# CadSoftElectronic.net
KiCad netlist of a schematic drawn in EAGLE
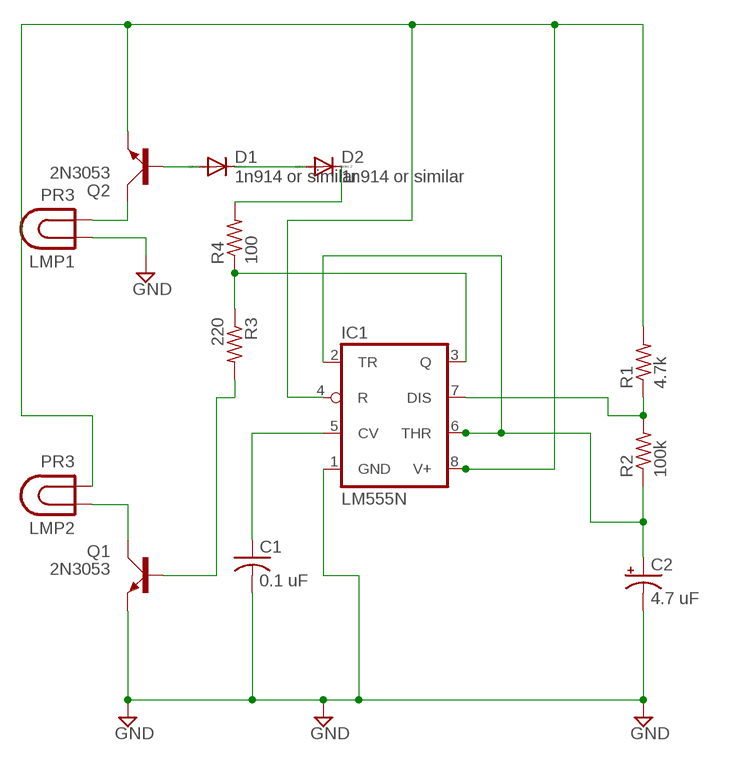
[diagram p0: schematic, sheet 1]

(export (version "E")
  (design (tool "Eeschema 10.0.6"))
  (components
    (comp (ref "C1")
      (value "0.1 uF")
      (footprint "eagle-import:C050-025X075")
      (libsource (lib "eagle-import") (part "C-US050-025X075"))
    )
    (comp (ref "C2")
      (value "4.7 uF")
      (footprint "eagle-import:E5-5")
      (libsource (lib "eagle-import") (part "CPOL-USE5-5"))
    )
    (comp (ref "D1")
      (value "1n914 or similar")
      (footprint "eagle-import:D-2.5")
      (libsource (lib "eagle-import") (part "DIODE-D-2.5"))
    )
    (comp (ref "D2")
      (value "1n914 or similar")
      (footprint "eagle-import:D-2.5")
      (libsource (lib "eagle-import") (part "DIODE-D-2.5"))
    )
    (comp (ref "IC1")
      (value "LM555N")
      (footprint "eagle-import:DIL08")
      (libsource (lib "eagle-import") (part "555NLM"))
    )
    (comp (ref "LMP1")
      (value "PR3")
      (footprint "eagle-import:LDH-5R")
      (libsource (lib "eagle-import") (part "LAMP"))
    )
    (comp (ref "LMP2")
      (value "PR3")
      (footprint "eagle-import:LDH-5R")
      (libsource (lib "eagle-import") (part "LAMP"))
    )
    (comp (ref "Q1")
      (value "2N3053")
      (footprint "eagle-import:TO39")
      (libsource (lib "eagle-import") (part "2N3053"))
    )
    (comp (ref "Q2")
      (value "2N3053")
      (footprint "eagle-import:TO39")
      (libsource (lib "eagle-import") (part "2N3053"))
    )
    (comp (ref "R1")
      (value "4.7k")
      (footprint "eagle-import:0207_2V")
      (libsource (lib "eagle-import") (part "R-US_0207/2V"))
    )
    (comp (ref "R2")
      (value "100k")
      (footprint "eagle-import:0207_2V")
      (libsource (lib "eagle-import") (part "R-US_0207/2V"))
    )
    (comp (ref "R3")
      (value "220")
      (footprint "eagle-import:0207_2V")
      (libsource (lib "eagle-import") (part "R-US_0207/2V"))
    )
    (comp (ref "R4")
      (value "100")
      (footprint "eagle-import:0207_2V")
      (libsource (lib "eagle-import") (part "R-US_0207/2V"))
    )
  )
  (nets
    (net (code "1") (name "GND") (class "Default")
      (node (ref "C1") (pin "2") (pinfunction "2_2") (pintype "passive"))
      (node (ref "C2") (pin "-") (pinfunction "-_-") (pintype "passive"))
      (node (ref "IC1") (pin "1") (pinfunction "GND_1") (pintype "power_in"))
      (node (ref "LMP1") (pin "1") (pinfunction "1_1") (pintype "passive"))
      (node (ref "Q1") (pin "1") (pinfunction "E_1") (pintype "passive"))
    )
    (net (code "2") (name "Net-(D1-PadC)") (class "Default")
      (node (ref "D1") (pin "C") (pinfunction "C_C") (pintype "passive"))
      (node (ref "D2") (pin "A") (pinfunction "A_A") (pintype "passive"))
    )
    (net (code "3") (name "Net-(D2-PadC)") (class "Default")
      (node (ref "D2") (pin "C") (pinfunction "C_C") (pintype "passive"))
      (node (ref "R4") (pin "2") (pinfunction "2_2") (pintype "passive"))
    )
    (net (code "4") (name "Net-(IC1-CV)") (class "Default")
      (node (ref "C1") (pin "1") (pinfunction "1_1") (pintype "passive"))
      (node (ref "IC1") (pin "5") (pinfunction "CV_5") (pintype "input"))
    )
    (net (code "5") (name "Net-(IC1-DIS)") (class "Default")
      (node (ref "IC1") (pin "7") (pinfunction "DIS_7") (pintype "input"))
      (node (ref "R1") (pin "1") (pinfunction "1_1") (pintype "passive"))
      (node (ref "R2") (pin "2") (pinfunction "2_2") (pintype "passive"))
    )
    (net (code "6") (name "Net-(IC1-Q)") (class "Default")
      (node (ref "IC1") (pin "3") (pinfunction "Q_3") (pintype "output"))
      (node (ref "R3") (pin "1") (pinfunction "1_1") (pintype "passive"))
      (node (ref "R4") (pin "1") (pinfunction "1_1") (pintype "passive"))
    )
    (net (code "7") (name "Net-(IC1-R)") (class "Default")
      (node (ref "IC1") (pin "4") (pinfunction "R_4") (pintype "input"))
      (node (ref "IC1") (pin "8") (pinfunction "V+_8") (pintype "power_in"))
      (node (ref "LMP2") (pin "2") (pinfunction "2_2") (pintype "passive"))
      (node (ref "Q2") (pin "1") (pinfunction "E_1") (pintype "passive"))
      (node (ref "R1") (pin "2") (pinfunction "2_2") (pintype "passive"))
    )
    (net (code "8") (name "Net-(IC1-THR)") (class "Default")
      (node (ref "C2") (pin "+") (pinfunction "+_+") (pintype "passive"))
      (node (ref "IC1") (pin "2") (pinfunction "TR_2") (pintype "input"))
      (node (ref "IC1") (pin "6") (pinfunction "THR_6") (pintype "input"))
      (node (ref "R2") (pin "1") (pinfunction "1_1") (pintype "passive"))
    )
    (net (code "9") (name "Net-(Q1-B)") (class "Default")
      (node (ref "Q1") (pin "2") (pinfunction "B_2") (pintype "passive"))
      (node (ref "R3") (pin "2") (pinfunction "2_2") (pintype "passive"))
    )
    (net (code "10") (name "Net-(Q1-C)") (class "Default")
      (node (ref "LMP2") (pin "1") (pinfunction "1_1") (pintype "passive"))
      (node (ref "Q1") (pin "3") (pinfunction "C_3") (pintype "passive"))
    )
    (net (code "11") (name "Net-(Q2-B)") (class "Default")
      (node (ref "D1") (pin "A") (pinfunction "A_A") (pintype "passive"))
      (node (ref "Q2") (pin "2") (pinfunction "B_2") (pintype "passive"))
    )
    (net (code "12") (name "Net-(Q2-C)") (class "Default")
      (node (ref "LMP1") (pin "2") (pinfunction "2_2") (pintype "passive"))
      (node (ref "Q2") (pin "3") (pinfunction "C_3") (pintype "passive"))
    )
  )
)
